# POWER.net
KiCad netlist of a schematic drawn in Altium Designer
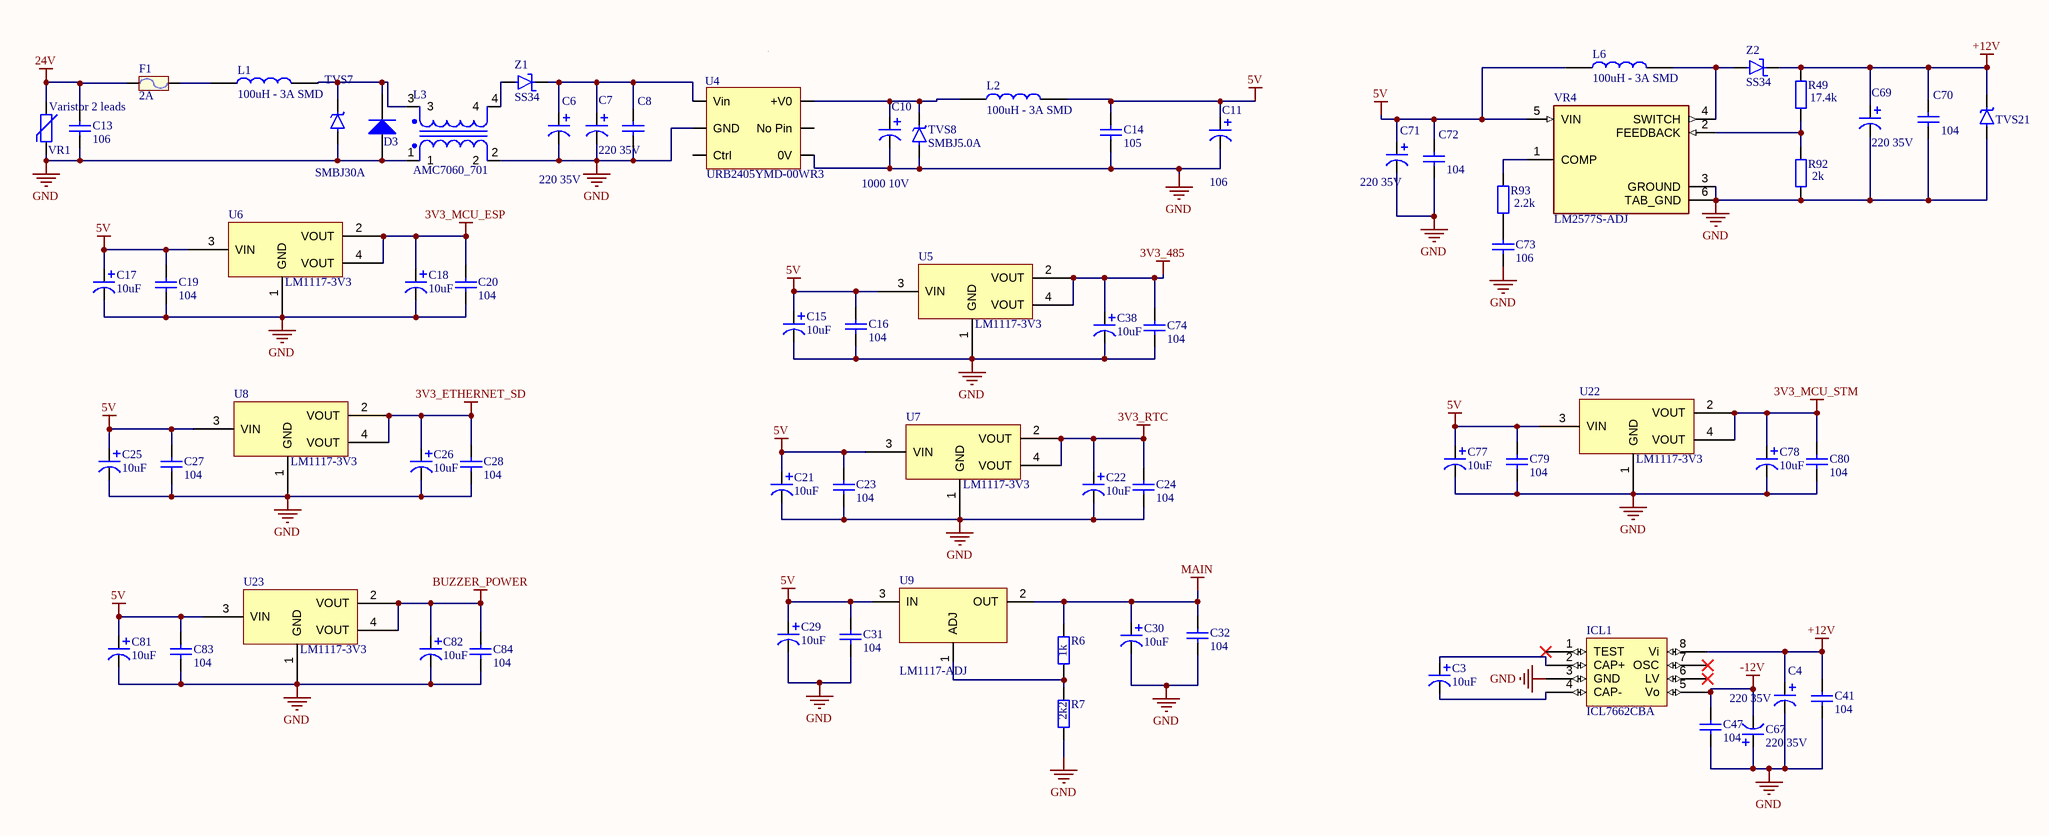
[diagram p0: POWER.SchDoc]

(export (version "E")
  (design (tool "Eeschema 10.0.6"))
  (components
    (comp (ref "C3")
      (value "10uF")
      (footprint "1206_CAP")
      (description "Polarized Capacitor")
      (libsource (lib "") (part "Polarized Capacitor_1"))
    )
    (comp (ref "C4")
      (value "220 35V")
      (footprint "8x12 radial capacitor")
      (description "Polarized Capacitor")
      (libsource (lib "") (part "Polarized Capacitor_1"))
    )
    (comp (ref "C6")
      (value "220 35V")
      (footprint "8x12 radial capacitor")
      (description "Polarized Capacitor")
      (libsource (lib "") (part "Polarized Capacitor_1"))
    )
    (comp (ref "C7")
      (value "220 35V")
      (footprint "8x12 radial capacitor")
      (description "Polarized Capacitor")
      (libsource (lib "") (part "Polarized Capacitor_1"))
    )
    (comp (ref "C8") (value "105") (footprint "0805_Cap") (libsource (lib "CMN") (part "Ceramic Capacitor")))
    (comp (ref "C10")
      (value "1000 10V")
      (footprint "8x12 radial capacitor")
      (description "Polarized Capacitor")
      (libsource (lib "") (part "Polarized Capacitor_1"))
    )
    (comp (ref "C11")
      (value "106")
      (footprint "1206_CAP")
      (description "Polarized Capacitor")
      (libsource (lib "") (part "Polarized Capacitor_1"))
    )
    (comp (ref "C13") (value "106") (footprint "1206_CAP") (libsource (lib "CMN") (part "Ceramic Capacitor")))
    (comp (ref "C14") (value "105") (footprint "1206_CAP") (libsource (lib "CMN") (part "Ceramic Capacitor")))
    (comp (ref "C15")
      (value "10uF")
      (footprint "1206_CAP")
      (description "Polarized Capacitor")
      (libsource (lib "") (part "Polarized Capacitor_1"))
    )
    (comp (ref "C16") (value "104") (footprint "0603_Cap") (libsource (lib "CMN") (part "Ceramic Capacitor")))
    (comp (ref "C17")
      (value "10uF")
      (footprint "1206_CAP")
      (description "Polarized Capacitor")
      (libsource (lib "") (part "Polarized Capacitor_1"))
    )
    (comp (ref "C18")
      (value "10uF")
      (footprint "1206_CAP")
      (description "Polarized Capacitor")
      (libsource (lib "") (part "Polarized Capacitor_1"))
    )
    (comp (ref "C19") (value "104") (footprint "0603_Cap") (libsource (lib "CMN") (part "Ceramic Capacitor")))
    (comp (ref "C20") (value "104") (footprint "0603_Cap") (libsource (lib "CMN") (part "Ceramic Capacitor")))
    (comp (ref "C21")
      (value "10uF")
      (footprint "1206_CAP")
      (description "Polarized Capacitor")
      (libsource (lib "") (part "Polarized Capacitor_1"))
    )
    (comp (ref "C22")
      (value "10uF")
      (footprint "1206_CAP")
      (description "Polarized Capacitor")
      (libsource (lib "") (part "Polarized Capacitor_1"))
    )
    (comp (ref "C23") (value "104") (footprint "0603_Cap") (libsource (lib "CMN") (part "Ceramic Capacitor")))
    (comp (ref "C24") (value "104") (footprint "0603_Cap") (libsource (lib "CMN") (part "Ceramic Capacitor")))
    (comp (ref "C25")
      (value "10uF")
      (footprint "1206_CAP")
      (description "Polarized Capacitor")
      (libsource (lib "") (part "Polarized Capacitor_1"))
    )
    (comp (ref "C26")
      (value "10uF")
      (footprint "1206_CAP")
      (description "Polarized Capacitor")
      (libsource (lib "") (part "Polarized Capacitor_1"))
    )
    (comp (ref "C27") (value "104") (footprint "0603_Cap") (libsource (lib "CMN") (part "Ceramic Capacitor")))
    (comp (ref "C28") (value "104") (footprint "0603_Cap") (libsource (lib "CMN") (part "Ceramic Capacitor")))
    (comp (ref "C29")
      (value "10uF")
      (footprint "1206_CAP")
      (description "Polarized Capacitor")
      (libsource (lib "") (part "Polarized Capacitor_1"))
    )
    (comp (ref "C30")
      (value "10uF")
      (footprint "1206_CAP")
      (description "Polarized Capacitor")
      (libsource (lib "") (part "Polarized Capacitor_1"))
    )
    (comp (ref "C31") (value "104") (footprint "0603_Cap") (libsource (lib "CMN") (part "Ceramic Capacitor")))
    (comp (ref "C32") (value "104") (footprint "0603_Cap") (libsource (lib "CMN") (part "Ceramic Capacitor")))
    (comp (ref "C38")
      (value "10uF")
      (footprint "1206_CAP")
      (description "Polarized Capacitor")
      (libsource (lib "") (part "Polarized Capacitor_1"))
    )
    (comp (ref "C41") (value "104") (footprint "0603_Cap") (libsource (lib "CMN") (part "Ceramic Capacitor")))
    (comp (ref "C47") (value "104") (footprint "0603_Cap") (libsource (lib "CMN") (part "Ceramic Capacitor")))
    (comp (ref "C67")
      (value "220 35V")
      (footprint "8x12 radial capacitor")
      (description "Polarized Capacitor")
      (libsource (lib "CMN") (part "Polarized Capacitor"))
    )
    (comp (ref "C69")
      (value "220 35V")
      (footprint "8x12 radial capacitor")
      (description "Polarized Capacitor")
      (libsource (lib "") (part "Polarized Capacitor_1"))
    )
    (comp (ref "C70") (value "104") (footprint "0805_Cap") (libsource (lib "CMN") (part "Ceramic Capacitor")))
    (comp (ref "C71")
      (value "220 35V")
      (footprint "8x12 radial capacitor")
      (description "Polarized Capacitor")
      (libsource (lib "") (part "Polarized Capacitor_1"))
    )
    (comp (ref "C72") (value "104") (footprint "0805_Cap") (libsource (lib "CMN") (part "Ceramic Capacitor")))
    (comp (ref "C73") (value "106") (footprint "1206_CAP") (libsource (lib "CMN") (part "Ceramic Capacitor")))
    (comp (ref "C74") (value "104") (footprint "0603_Cap") (libsource (lib "CMN") (part "Ceramic Capacitor")))
    (comp (ref "C77")
      (value "10uF")
      (footprint "1206_CAP")
      (description "Polarized Capacitor")
      (libsource (lib "") (part "Polarized Capacitor_1"))
    )
    (comp (ref "C78")
      (value "10uF")
      (footprint "1206_CAP")
      (description "Polarized Capacitor")
      (libsource (lib "") (part "Polarized Capacitor_1"))
    )
    (comp (ref "C79") (value "104") (footprint "0603_Cap") (libsource (lib "CMN") (part "Ceramic Capacitor")))
    (comp (ref "C80") (value "104") (footprint "0603_Cap") (libsource (lib "CMN") (part "Ceramic Capacitor")))
    (comp (ref "C81")
      (value "10uF")
      (footprint "1206_CAP")
      (description "Polarized Capacitor")
      (libsource (lib "") (part "Polarized Capacitor_1"))
    )
    (comp (ref "C82")
      (value "10uF")
      (footprint "1206_CAP")
      (description "Polarized Capacitor")
      (libsource (lib "") (part "Polarized Capacitor_1"))
    )
    (comp (ref "C83") (value "104") (footprint "0603_Cap") (libsource (lib "CMN") (part "Ceramic Capacitor")))
    (comp (ref "C84") (value "104") (footprint "0603_Cap") (libsource (lib "CMN") (part "Ceramic Capacitor")))
    (comp (ref "D3") (value "RS3M") (footprint "SMC - DO-214") (libsource (lib "CMN") (part "Diode")))
    (comp (ref "F1")
      (value "2A")
      (footprint "Fuse4")
      (description "Fuse")
      (fields (field (name "DESIGNED BY") "VanDungEvn"))
      (libsource (lib "KhanhBK_SCH_Library_1") (part "Fuse"))
    )
    (comp (ref "ICL1")
      (value "ICL7662CBA")
      (footprint "ICL7662CBA:ICL7662CBA")
      (libsource (lib "ICB7662CBA") (part "ICL7662CBA"))
    )
    (comp (ref "L1")
      (value "100uH - 3A SMD")
      (footprint "Cuon Cam 12x12x10")
      (description "Dán")
      (libsource (lib "Cuon Cam") (part "CUON CAM 100uH SMD"))
    )
    (comp (ref "L2")
      (value "100uH - 3A SMD")
      (footprint "Cuon Cam 12x12x10")
      (description "Dán")
      (libsource (lib "Cuon Cam") (part "CUON CAM 100uH SMD"))
    )
    (comp (ref "L3")
      (value "AMC7060_701")
      (footprint "Double inductor")
      (description "Common mode choke\r\ncuon cam xuyen")
      (libsource (lib "CMN") (part "inductor_1"))
    )
    (comp (ref "L6")
      (value "100uH - 3A SMD")
      (footprint "Cuon Cam 12x12x10")
      (description "Dán")
      (libsource (lib "Cuon Cam") (part "CUON CAM 100uH SMD"))
    )
    (comp (ref "R6") (value "1k") (footprint "0603_Res") (libsource (lib "CMN") (part "Resistor")))
    (comp (ref "R7") (value "2k2") (footprint "0603_Res") (libsource (lib "CMN") (part "Resistor")))
    (comp (ref "R49") (value "17.4k") (footprint "0603_Res") (libsource (lib "CMN") (part "Resistor")))
    (comp (ref "R92") (value "2k") (footprint "0603_Res") (libsource (lib "CMN") (part "Resistor")))
    (comp (ref "R93") (value "2.2k") (footprint "0603_Res") (libsource (lib "CMN") (part "Resistor")))
    (comp (ref "TVS7")
      (value "SMBJ30A")
      (footprint "SMC - DO-214")
      (libsource (lib "CMN") (part "TVS Uni Diode"))
    )
    (comp (ref "TVS8")
      (value "SMBJ5.0A")
      (footprint "SMB - DO-214AA")
      (libsource (lib "CMN") (part "TVS Uni Diode"))
    )
    (comp (ref "TVS21")
      (value "SMBJ30A")
      (footprint "SMC - DO-214")
      (libsource (lib "CMN") (part "TVS Uni Diode"))
    )
    (comp (ref "U4")
      (value "URB2405YMD-00WR3")
      (footprint "URB2405YMD-xxWR3")
      (libsource (lib "CMN") (part "URB2405YMD-00WR3"))
    )
    (comp (ref "U5") (value "LM1117-3V3") (footprint "SOT-223") (libsource (lib "CMN") (part "LM1117-3V3")))
    (comp (ref "U6") (value "LM1117-3V3") (footprint "SOT-223") (libsource (lib "CMN") (part "LM1117-3V3")))
    (comp (ref "U7") (value "LM1117-3V3") (footprint "SOT-223") (libsource (lib "CMN") (part "LM1117-3V3")))
    (comp (ref "U8") (value "LM1117-3V3") (footprint "SOT-223") (libsource (lib "CMN") (part "LM1117-3V3")))
    (comp (ref "U9")
      (value "LM1117-ADJ")
      (footprint "LM1117-SOP")
      (description "800mA Low-Dropout Linear Regulator")
      (fields (field (name "CREATOR") "Nguyen Ba Bien"))
      (libsource (lib "KhanhBK_SCH_Library_2") (part "LM1117-ADJ"))
    )
    (comp (ref "U22") (value "LM1117-3V3") (footprint "SOT-223") (libsource (lib "CMN") (part "LM1117-3V3")))
    (comp (ref "U23") (value "LM1117-3V3") (footprint "SOT-223") (libsource (lib "CMN") (part "LM1117-3V3")))
    (comp (ref "VR1")
      (value "Varistor 2 leads")
      (footprint "Varistor")
      (libsource (lib "CMN") (part "Varistor"))
    )
    (comp (ref "VR4")
      (value "LM2577S-ADJ")
      (footprint "TO170P1524X483-6N")
      (fields (field (name "MF") "Texas Instruments"))
      (libsource (lib "LM2577S-ADJ") (part "LM2577S-ADJ"))
    )
    (comp (ref "Z1")
      (value "SS34")
      (footprint "SMB - DO-214AA")
      (fields (field (name "MP") "1SMA5926") (field (name "MF") "Taiwan Semiconductor"))
      (libsource (lib "CMN") (part "Zenner Diode"))
    )
    (comp (ref "Z2")
      (value "SS34")
      (footprint "SMB - DO-214AA")
      (fields (field (name "MP") "1SMA5926") (field (name "MF") "Taiwan Semiconductor"))
      (libsource (lib "CMN") (part "Zenner Diode"))
    )
  )
  (nets
    (net (code "1") (name "+12V") (class "Default")
      (node (ref "C4") (pin "1") (pinfunction "1_1") (pintype "passive"))
      (node (ref "C41") (pin "1") (pinfunction "1_1") (pintype "passive"))
      (node (ref "C69") (pin "1") (pinfunction "1_1") (pintype "passive"))
      (node (ref "C70") (pin "1") (pinfunction "1_1") (pintype "passive"))
      (node (ref "ICL1") (pin "8") (pinfunction "Vi_8") (pintype "bidirectional"))
      (node (ref "R49") (pin "2") (pinfunction "2_2") (pintype "passive"))
      (node (ref "TVS21") (pin "1") (pinfunction "1_1") (pintype "passive"))
      (node (ref "Z2") (pin "1") (pinfunction "1_1") (pintype "passive"))
    )
    (net (code "2") (name "-12V") (class "Default")
      (node (ref "C47") (pin "1") (pinfunction "1_1") (pintype "passive"))
      (node (ref "C67") (pin "2") (pinfunction "2_2") (pintype "passive"))
      (node (ref "ICL1") (pin "5") (pinfunction "Vo_5") (pintype "bidirectional"))
    )
    (net (code "3") (name "3V3_485") (class "Default")
      (node (ref "C38") (pin "1") (pinfunction "1_1") (pintype "passive"))
      (node (ref "C74") (pin "1") (pinfunction "1_1") (pintype "passive"))
      (node (ref "U5") (pin "2") (pinfunction "VOUT_2") (pintype "passive"))
      (node (ref "U5") (pin "4") (pinfunction "VOUT_4") (pintype "passive"))
    )
    (net (code "4") (name "3V3_ETHERNET_SD") (class "Default")
      (node (ref "C26") (pin "1") (pinfunction "1_1") (pintype "passive"))
      (node (ref "C28") (pin "1") (pinfunction "1_1") (pintype "passive"))
      (node (ref "U8") (pin "2") (pinfunction "VOUT_2") (pintype "passive"))
      (node (ref "U8") (pin "4") (pinfunction "VOUT_4") (pintype "passive"))
    )
    (net (code "5") (name "3V3_MCU_ESP") (class "Default")
      (node (ref "C18") (pin "1") (pinfunction "1_1") (pintype "passive"))
      (node (ref "C20") (pin "1") (pinfunction "1_1") (pintype "passive"))
      (node (ref "U6") (pin "2") (pinfunction "VOUT_2") (pintype "passive"))
      (node (ref "U6") (pin "4") (pinfunction "VOUT_4") (pintype "passive"))
    )
    (net (code "6") (name "3V3_MCU_STM") (class "Default")
      (node (ref "C78") (pin "1") (pinfunction "1_1") (pintype "passive"))
      (node (ref "C80") (pin "1") (pinfunction "1_1") (pintype "passive"))
      (node (ref "U22") (pin "2") (pinfunction "VOUT_2") (pintype "passive"))
      (node (ref "U22") (pin "4") (pinfunction "VOUT_4") (pintype "passive"))
    )
    (net (code "7") (name "3V3_RTC") (class "Default")
      (node (ref "C22") (pin "1") (pinfunction "1_1") (pintype "passive"))
      (node (ref "C24") (pin "1") (pinfunction "1_1") (pintype "passive"))
      (node (ref "U7") (pin "2") (pinfunction "VOUT_2") (pintype "passive"))
      (node (ref "U7") (pin "4") (pinfunction "VOUT_4") (pintype "passive"))
    )
    (net (code "8") (name "5V") (class "Default")
      (node (ref "C11") (pin "1") (pinfunction "1_1") (pintype "passive"))
      (node (ref "C14") (pin "1") (pinfunction "1_1") (pintype "passive"))
      (node (ref "C15") (pin "1") (pinfunction "1_1") (pintype "passive"))
      (node (ref "C16") (pin "1") (pinfunction "1_1") (pintype "passive"))
      (node (ref "C17") (pin "1") (pinfunction "1_1") (pintype "passive"))
      (node (ref "C19") (pin "1") (pinfunction "1_1") (pintype "passive"))
      (node (ref "C21") (pin "1") (pinfunction "1_1") (pintype "passive"))
      (node (ref "C23") (pin "1") (pinfunction "1_1") (pintype "passive"))
      (node (ref "C25") (pin "1") (pinfunction "1_1") (pintype "passive"))
      (node (ref "C27") (pin "1") (pinfunction "1_1") (pintype "passive"))
      (node (ref "C29") (pin "1") (pinfunction "1_1") (pintype "passive"))
      (node (ref "C31") (pin "1") (pinfunction "1_1") (pintype "passive"))
      (node (ref "C71") (pin "1") (pinfunction "1_1") (pintype "passive"))
      (node (ref "C72") (pin "1") (pinfunction "1_1") (pintype "passive"))
      (node (ref "C77") (pin "1") (pinfunction "1_1") (pintype "passive"))
      (node (ref "C79") (pin "1") (pinfunction "1_1") (pintype "passive"))
      (node (ref "C81") (pin "1") (pinfunction "1_1") (pintype "passive"))
      (node (ref "C83") (pin "1") (pinfunction "1_1") (pintype "passive"))
      (node (ref "L2") (pin "2") (pinfunction "2_2") (pintype "passive"))
      (node (ref "L6") (pin "1") (pinfunction "1_1") (pintype "passive"))
      (node (ref "U22") (pin "3") (pinfunction "VIN_3") (pintype "passive"))
      (node (ref "U23") (pin "3") (pinfunction "VIN_3") (pintype "passive"))
      (node (ref "U5") (pin "3") (pinfunction "VIN_3") (pintype "passive"))
      (node (ref "U6") (pin "3") (pinfunction "VIN_3") (pintype "passive"))
      (node (ref "U7") (pin "3") (pinfunction "VIN_3") (pintype "passive"))
      (node (ref "U8") (pin "3") (pinfunction "VIN_3") (pintype "passive"))
      (node (ref "U9") (pin "3") (pinfunction "IN_3") (pintype "passive"))
      (node (ref "VR4") (pin "5") (pinfunction "VIN_5") (pintype "input"))
    )
    (net (code "9") (name "24V") (class "Default")
      (node (ref "C13") (pin "1") (pinfunction "1_1") (pintype "passive"))
      (node (ref "F1") (pin "1") (pinfunction "1_1") (pintype "passive"))
      (node (ref "VR1") (pin "1") (pinfunction "1_1") (pintype "passive"))
    )
    (net (code "10") (name "BUZZER_POWER") (class "Default")
      (node (ref "C82") (pin "1") (pinfunction "1_1") (pintype "passive"))
      (node (ref "C84") (pin "1") (pinfunction "1_1") (pintype "passive"))
      (node (ref "U23") (pin "2") (pinfunction "VOUT_2") (pintype "passive"))
      (node (ref "U23") (pin "4") (pinfunction "VOUT_4") (pintype "passive"))
    )
    (net (code "11") (name "GND") (class "Default")
      (node (ref "C10") (pin "2") (pinfunction "2_2") (pintype "passive"))
      (node (ref "C11") (pin "2") (pinfunction "2_2") (pintype "passive"))
      (node (ref "C13") (pin "2") (pinfunction "2_2") (pintype "passive"))
      (node (ref "C14") (pin "2") (pinfunction "2_2") (pintype "passive"))
      (node (ref "C15") (pin "2") (pinfunction "2_2") (pintype "passive"))
      (node (ref "C16") (pin "2") (pinfunction "2_2") (pintype "passive"))
      (node (ref "C17") (pin "2") (pinfunction "2_2") (pintype "passive"))
      (node (ref "C18") (pin "2") (pinfunction "2_2") (pintype "passive"))
      (node (ref "C19") (pin "2") (pinfunction "2_2") (pintype "passive"))
      (node (ref "C20") (pin "2") (pinfunction "2_2") (pintype "passive"))
      (node (ref "C21") (pin "2") (pinfunction "2_2") (pintype "passive"))
      (node (ref "C22") (pin "2") (pinfunction "2_2") (pintype "passive"))
      (node (ref "C23") (pin "2") (pinfunction "2_2") (pintype "passive"))
      (node (ref "C24") (pin "2") (pinfunction "2_2") (pintype "passive"))
      (node (ref "C25") (pin "2") (pinfunction "2_2") (pintype "passive"))
      (node (ref "C26") (pin "2") (pinfunction "2_2") (pintype "passive"))
      (node (ref "C27") (pin "2") (pinfunction "2_2") (pintype "passive"))
      (node (ref "C28") (pin "2") (pinfunction "2_2") (pintype "passive"))
      (node (ref "C29") (pin "2") (pinfunction "2_2") (pintype "passive"))
      (node (ref "C30") (pin "2") (pinfunction "2_2") (pintype "passive"))
      (node (ref "C31") (pin "2") (pinfunction "2_2") (pintype "passive"))
      (node (ref "C32") (pin "2") (pinfunction "2_2") (pintype "passive"))
      (node (ref "C38") (pin "2") (pinfunction "2_2") (pintype "passive"))
      (node (ref "C4") (pin "2") (pinfunction "2_2") (pintype "passive"))
      (node (ref "C41") (pin "2") (pinfunction "2_2") (pintype "passive"))
      (node (ref "C47") (pin "2") (pinfunction "2_2") (pintype "passive"))
      (node (ref "C6") (pin "2") (pinfunction "2_2") (pintype "passive"))
      (node (ref "C67") (pin "1") (pinfunction "1_1") (pintype "passive"))
      (node (ref "C69") (pin "2") (pinfunction "2_2") (pintype "passive"))
      (node (ref "C7") (pin "2") (pinfunction "2_2") (pintype "passive"))
      (node (ref "C70") (pin "2") (pinfunction "2_2") (pintype "passive"))
      (node (ref "C71") (pin "2") (pinfunction "2_2") (pintype "passive"))
      (node (ref "C72") (pin "2") (pinfunction "2_2") (pintype "passive"))
      (node (ref "C73") (pin "2") (pinfunction "2_2") (pintype "passive"))
      (node (ref "C74") (pin "2") (pinfunction "2_2") (pintype "passive"))
      (node (ref "C77") (pin "2") (pinfunction "2_2") (pintype "passive"))
      (node (ref "C78") (pin "2") (pinfunction "2_2") (pintype "passive"))
      (node (ref "C79") (pin "2") (pinfunction "2_2") (pintype "passive"))
      (node (ref "C8") (pin "2") (pinfunction "2_2") (pintype "passive"))
      (node (ref "C80") (pin "2") (pinfunction "2_2") (pintype "passive"))
      (node (ref "C81") (pin "2") (pinfunction "2_2") (pintype "passive"))
      (node (ref "C82") (pin "2") (pinfunction "2_2") (pintype "passive"))
      (node (ref "C83") (pin "2") (pinfunction "2_2") (pintype "passive"))
      (node (ref "C84") (pin "2") (pinfunction "2_2") (pintype "passive"))
      (node (ref "D3") (pin "2") (pinfunction "2_2") (pintype "passive"))
      (node (ref "ICL1") (pin "3") (pinfunction "GND_3") (pintype "bidirectional"))
      (node (ref "L3") (pin "1") (pinfunction "1_1") (pintype "passive"))
      (node (ref "L3") (pin "2") (pinfunction "2_2") (pintype "passive"))
      (node (ref "R7") (pin "1") (pinfunction "1_1") (pintype "passive"))
      (node (ref "R92") (pin "1") (pinfunction "1_1") (pintype "passive"))
      (node (ref "TVS21") (pin "2") (pinfunction "2_2") (pintype "passive"))
      (node (ref "TVS7") (pin "2") (pinfunction "2_2") (pintype "passive"))
      (node (ref "TVS8") (pin "2") (pinfunction "2_2") (pintype "passive"))
      (node (ref "U22") (pin "1") (pinfunction "GND_1") (pintype "passive"))
      (node (ref "U23") (pin "1") (pinfunction "GND_1") (pintype "passive"))
      (node (ref "U4") (pin "2") (pinfunction "GND_2") (pintype "passive"))
      (node (ref "U4") (pin "6") (pinfunction "0V_6") (pintype "passive"))
      (node (ref "U5") (pin "1") (pinfunction "GND_1") (pintype "passive"))
      (node (ref "U6") (pin "1") (pinfunction "GND_1") (pintype "passive"))
      (node (ref "U7") (pin "1") (pinfunction "GND_1") (pintype "passive"))
      (node (ref "U8") (pin "1") (pinfunction "GND_1") (pintype "passive"))
      (node (ref "VR1") (pin "2") (pinfunction "2_2") (pintype "passive"))
      (node (ref "VR4") (pin "3") (pinfunction "GROUND_3") (pintype "power_in"))
      (node (ref "VR4") (pin "6") (pinfunction "TAB_GND_6") (pintype "power_in"))
    )
    (net (code "12") (name "MAIN") (class "Default")
      (node (ref "C30") (pin "1") (pinfunction "1_1") (pintype "passive"))
      (node (ref "C32") (pin "1") (pinfunction "1_1") (pintype "passive"))
      (node (ref "R6") (pin "2") (pinfunction "2_2") (pintype "passive"))
      (node (ref "U9") (pin "2") (pinfunction "OUT_2") (pintype "passive"))
    )
    (net (code "13") (name "Net-(C73-Pad1)") (class "Default")
      (node (ref "C73") (pin "1") (pinfunction "1_1") (pintype "passive"))
      (node (ref "R93") (pin "1") (pinfunction "1_1") (pintype "passive"))
    )
    (net (code "14") (name "Net-(D3-Pad1)") (class "Default")
      (node (ref "D3") (pin "1") (pinfunction "1_1") (pintype "passive"))
      (node (ref "L1") (pin "2") (pinfunction "2_2") (pintype "passive"))
      (node (ref "L3") (pin "3") (pinfunction "3_3") (pintype "passive"))
      (node (ref "TVS7") (pin "1") (pinfunction "1_1") (pintype "passive"))
    )
    (net (code "15") (name "Net-(F1-Pad2)") (class "Default")
      (node (ref "F1") (pin "2") (pinfunction "2_2") (pintype "passive"))
      (node (ref "L1") (pin "1") (pinfunction "1_1") (pintype "passive"))
    )
    (net (code "16") (name "Net-(ICL1-CAP+)") (class "Default")
      (node (ref "C3") (pin "1") (pinfunction "1_1") (pintype "passive"))
      (node (ref "ICL1") (pin "2") (pinfunction "CAP+_2") (pintype "bidirectional"))
    )
    (net (code "17") (name "Net-(ICL1-CAP-)") (class "Default")
      (node (ref "C3") (pin "2") (pinfunction "2_2") (pintype "passive"))
      (node (ref "ICL1") (pin "4") (pinfunction "CAP-_4") (pintype "bidirectional"))
    )
    (net (code "18") (name "Net-(L3-Pad4)") (class "Default")
      (node (ref "L3") (pin "4") (pinfunction "4_4") (pintype "passive"))
      (node (ref "Z1") (pin "2") (pinfunction "2_2") (pintype "passive"))
    )
    (net (code "19") (name "Net-(U4-+V0)") (class "Default")
      (node (ref "C10") (pin "1") (pinfunction "1_1") (pintype "passive"))
      (node (ref "L2") (pin "1") (pinfunction "1_1") (pintype "passive"))
      (node (ref "TVS8") (pin "1") (pinfunction "1_1") (pintype "passive"))
      (node (ref "U4") (pin "4") (pinfunction "+V0_4") (pintype "passive"))
    )
    (net (code "20") (name "Net-(U4-Vin)") (class "Default")
      (node (ref "C6") (pin "1") (pinfunction "1_1") (pintype "passive"))
      (node (ref "C7") (pin "1") (pinfunction "1_1") (pintype "passive"))
      (node (ref "C8") (pin "1") (pinfunction "1_1") (pintype "passive"))
      (node (ref "U4") (pin "3") (pinfunction "Vin_3") (pintype "passive"))
      (node (ref "Z1") (pin "1") (pinfunction "1_1") (pintype "passive"))
    )
    (net (code "21") (name "Net-(U9-ADJ)") (class "Default")
      (node (ref "R6") (pin "1") (pinfunction "1_1") (pintype "passive"))
      (node (ref "R7") (pin "2") (pinfunction "2_2") (pintype "passive"))
      (node (ref "U9") (pin "1") (pinfunction "ADJ_1") (pintype "passive"))
    )
    (net (code "22") (name "Net-(VR4-COMP)") (class "Default")
      (node (ref "R93") (pin "2") (pinfunction "2_2") (pintype "passive"))
      (node (ref "VR4") (pin "1") (pinfunction "COMP_1") (pintype "passive"))
    )
    (net (code "23") (name "Net-(VR4-FEEDBACK)") (class "Default")
      (node (ref "R49") (pin "1") (pinfunction "1_1") (pintype "passive"))
      (node (ref "R92") (pin "2") (pinfunction "2_2") (pintype "passive"))
      (node (ref "VR4") (pin "2") (pinfunction "FEEDBACK_2") (pintype "input"))
    )
    (net (code "24") (name "Net-(VR4-SWITCH)") (class "Default")
      (node (ref "L6") (pin "2") (pinfunction "2_2") (pintype "passive"))
      (node (ref "VR4") (pin "4") (pinfunction "SWITCH_4") (pintype "output"))
      (node (ref "Z2") (pin "2") (pinfunction "2_2") (pintype "passive"))
    )
    (net (code "25") (name "unconnected-(ICL1-LV-Pad6)") (class "Default")
      (node (ref "ICL1") (pin "6") (pinfunction "LV_6") (pintype "bidirectional+no_connect"))
    )
    (net (code "26") (name "unconnected-(ICL1-OSC-Pad7)") (class "Default")
      (node (ref "ICL1") (pin "7") (pinfunction "OSC_7") (pintype "bidirectional+no_connect"))
    )
    (net (code "27") (name "unconnected-(ICL1-TEST-Pad1)") (class "Default")
      (node (ref "ICL1") (pin "1") (pinfunction "TEST_1") (pintype "bidirectional+no_connect"))
    )
    (net (code "28") (name "unconnected-(U4-Ctrl-Pad1)") (class "Default")
      (node (ref "U4") (pin "1") (pinfunction "Ctrl_1") (pintype "passive"))
    )
    (net (code "29") (name "unconnected-(U4-No_Pin-Pad5)") (class "Default")
      (node (ref "U4") (pin "5") (pinfunction "No_Pin_5") (pintype "passive"))
    )
  )
)
